# timer_mic.net
KiCad netlist of a schematic drawn in Altium Designer
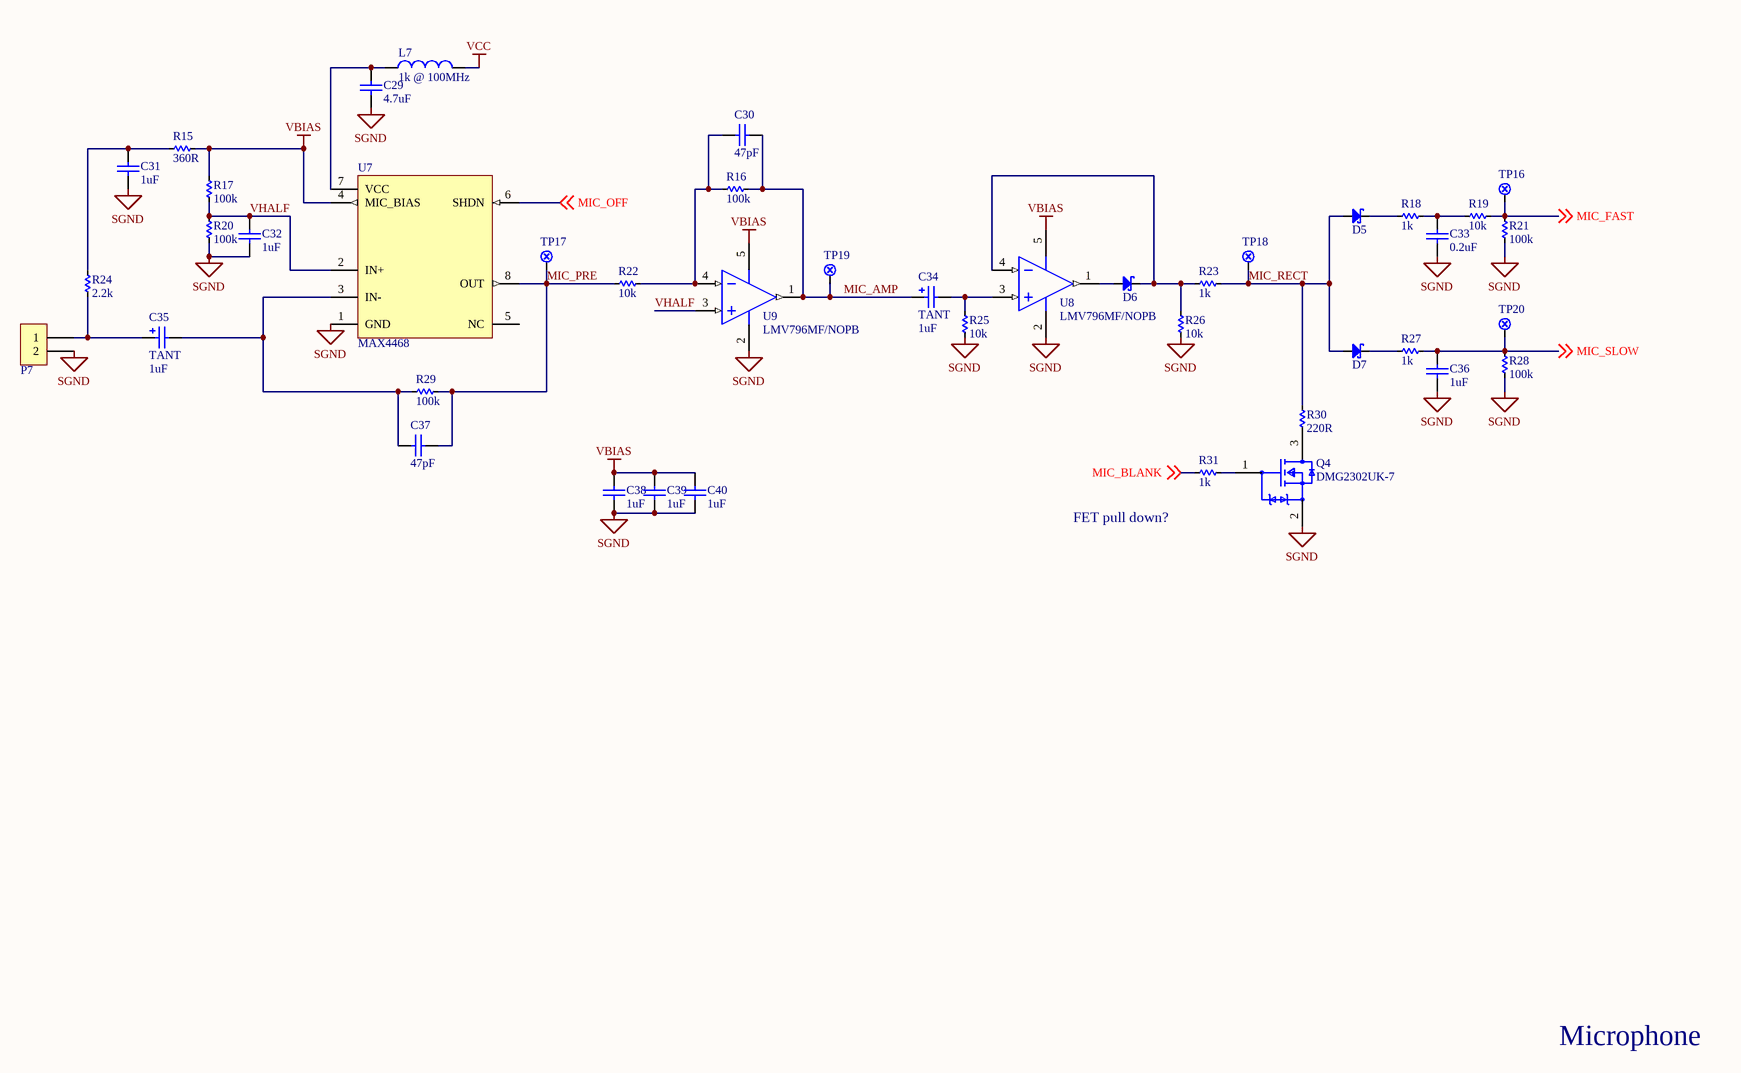
[diagram p0: timer_mic.SchDoc]

(export (version "E")
  (design (tool "Eeschema 10.0.6"))
  (components
    (comp (ref "C29")
      (value "4.7uF")
      (footprint "C0805/2012")
      (description "Capacitor")
      (fields (field (name "TOLERANCE") "x%") (field (name "VOLTAGE") "6.3V"))
      (libsource (lib "ZMPlib") (part "CAP"))
    )
    (comp (ref "C30")
      (value "47pF")
      (footprint "C0603/1608")
      (description "Capacitor")
      (fields (field (name "TOLERANCE") "x%") (field (name "VOLTAGE") "6.3V"))
      (libsource (lib "ZMPlib") (part "CAP"))
    )
    (comp (ref "C31")
      (value "1uF")
      (footprint "C0603/1608")
      (description "Capacitor")
      (fields (field (name "TOLERANCE") "x%") (field (name "VOLTAGE") "6.3V"))
      (libsource (lib "ZMPlib") (part "CAP"))
    )
    (comp (ref "C32")
      (value "1uF")
      (footprint "C0603/1608")
      (description "Capacitor")
      (fields (field (name "TOLERANCE") "x%") (field (name "VOLTAGE") "6.3V"))
      (libsource (lib "ZMPlib") (part "CAP"))
    )
    (comp (ref "C33")
      (value "0.2uF")
      (footprint "C0603/1608")
      (description "Capacitor")
      (fields (field (name "TOLERANCE") "x%") (field (name "VOLTAGE") "6.3V"))
      (libsource (lib "ZMPlib") (part "CAP"))
    )
    (comp (ref "C34")
      (value "1uF")
      (footprint "CP0805/2012")
      (description "Capacitor")
      (fields (field (name "VOLTAGE") "6.3V") (field (name "TOLERANCE") "x%") (field (name "TYPE") "TANT"))
      (libsource (lib "ZMPlib") (part "CAP_POL"))
    )
    (comp (ref "C35")
      (value "1uF")
      (footprint "CP0805/2012")
      (description "Capacitor")
      (fields (field (name "VOLTAGE") "6.3V") (field (name "TOLERANCE") "x%") (field (name "TYPE") "TANT"))
      (libsource (lib "ZMPlib") (part "CAP_POL"))
    )
    (comp (ref "C36")
      (value "1uF")
      (footprint "C0603/1608")
      (description "Capacitor")
      (fields (field (name "TOLERANCE") "x%") (field (name "VOLTAGE") "6.3V"))
      (libsource (lib "ZMPlib") (part "CAP"))
    )
    (comp (ref "C37")
      (value "47pF")
      (footprint "C0603/1608")
      (description "Capacitor")
      (fields (field (name "TOLERANCE") "x%") (field (name "VOLTAGE") "6.3V"))
      (libsource (lib "ZMPlib") (part "CAP"))
    )
    (comp (ref "C38")
      (value "1uF")
      (footprint "C0603/1608")
      (description "Capacitor")
      (fields (field (name "TOLERANCE") "x%") (field (name "VOLTAGE") "6.3V"))
      (libsource (lib "ZMPlib") (part "CAP"))
    )
    (comp (ref "C39")
      (value "1uF")
      (footprint "C0603/1608")
      (description "Capacitor")
      (fields (field (name "TOLERANCE") "x%") (field (name "VOLTAGE") "6.3V"))
      (libsource (lib "ZMPlib") (part "CAP"))
    )
    (comp (ref "C40")
      (value "1uF")
      (footprint "C0603/1608")
      (description "Capacitor")
      (fields (field (name "TOLERANCE") "x%") (field (name "VOLTAGE") "6.3V"))
      (libsource (lib "ZMPlib") (part "CAP"))
    )
    (comp (ref "D5")
      (value "DIODE_SCHOTTKY")
      (footprint "SOD-123")
      (description "Schottky Diode")
      (fields (field (name "VOLTAGE") "xV"))
      (libsource (lib "ZMPlib") (part "DIODE_SCHOTTKY"))
    )
    (comp (ref "D6")
      (value "DIODE_SCHOTTKY")
      (footprint "SOD-123")
      (description "Schottky Diode")
      (fields (field (name "VOLTAGE") "xV"))
      (libsource (lib "ZMPlib") (part "DIODE_SCHOTTKY"))
    )
    (comp (ref "D7")
      (value "DIODE_SCHOTTKY")
      (footprint "SOD-123")
      (description "Schottky Diode")
      (fields (field (name "VOLTAGE") "xV"))
      (libsource (lib "ZMPlib") (part "DIODE_SCHOTTKY"))
    )
    (comp (ref "L7")
      (value "1k @ 100MHz")
      (footprint "R0603/1608")
      (description "Inductor")
      (fields (field (name "Comment") "FERRITE"))
      (libsource (lib "ZMPlib") (part "IND"))
    )
    (comp (ref "P7")
      (value "SIL2")
      (footprint "PINS-2")
      (description "SIL package, 2 pins")
      (libsource (lib "ZMPlib") (part "SIL2"))
    )
    (comp (ref "Q4")
      (value "DMG2302UK-7")
      (footprint "FP-SOT23-MFG")
      (description "MOSFET N-CH 20V 2.8A SOT23")
      (fields
        (field (name "OCTOPART") "https://octopart.com/dmg2302uk-7-diodes+inc.-73850182")
        (field (name "MANUFACTURER") "Diodes Inc.")
      )
      (libsource (lib "Altium Content Vault") (part "87c0c04a04979492222792dd46c39c9"))
    )
    (comp (ref "R15")
      (value "360R")
      (footprint "R0603/1608")
      (description "Resistor")
      (fields (field (name "TOLERANCE") "x%") (field (name "Comment") "RES"))
      (libsource (lib "ZMPlib") (part "RES"))
    )
    (comp (ref "R16")
      (value "100k")
      (footprint "R0603/1608")
      (description "Resistor")
      (fields (field (name "TOLERANCE") "x%") (field (name "Comment") "RES"))
      (libsource (lib "ZMPlib") (part "RES"))
    )
    (comp (ref "R17")
      (value "100k")
      (footprint "R0603/1608")
      (description "Resistor")
      (fields (field (name "TOLERANCE") "x%") (field (name "Comment") "RES"))
      (libsource (lib "ZMPlib") (part "RES"))
    )
    (comp (ref "R18")
      (value "1k")
      (footprint "R0603/1608")
      (description "Resistor")
      (fields (field (name "TOLERANCE") "x%") (field (name "Comment") "RES"))
      (libsource (lib "ZMPlib") (part "RES"))
    )
    (comp (ref "R19")
      (value "10k")
      (footprint "R0603/1608")
      (description "Resistor")
      (fields (field (name "TOLERANCE") "x%") (field (name "Comment") "RES"))
      (libsource (lib "ZMPlib") (part "RES"))
    )
    (comp (ref "R20")
      (value "100k")
      (footprint "R0603/1608")
      (description "Resistor")
      (fields (field (name "TOLERANCE") "x%") (field (name "Comment") "RES"))
      (libsource (lib "ZMPlib") (part "RES"))
    )
    (comp (ref "R21")
      (value "100k")
      (footprint "R0603/1608")
      (description "Resistor")
      (fields (field (name "TOLERANCE") "x%") (field (name "Comment") "RES"))
      (libsource (lib "ZMPlib") (part "RES"))
    )
    (comp (ref "R22")
      (value "10k")
      (footprint "R0603/1608")
      (description "Resistor")
      (fields (field (name "TOLERANCE") "x%") (field (name "Comment") "RES"))
      (libsource (lib "ZMPlib") (part "RES"))
    )
    (comp (ref "R23")
      (value "1k")
      (footprint "R0603/1608")
      (description "Resistor")
      (fields (field (name "TOLERANCE") "x%") (field (name "Comment") "RES"))
      (libsource (lib "ZMPlib") (part "RES"))
    )
    (comp (ref "R24")
      (value "2.2k")
      (footprint "R0603/1608")
      (description "Resistor")
      (fields (field (name "TOLERANCE") "x%") (field (name "Comment") "RES"))
      (libsource (lib "ZMPlib") (part "RES"))
    )
    (comp (ref "R25")
      (value "10k")
      (footprint "R0603/1608")
      (description "Resistor")
      (fields (field (name "TOLERANCE") "x%") (field (name "Comment") "RES"))
      (libsource (lib "ZMPlib") (part "RES"))
    )
    (comp (ref "R26")
      (value "10k")
      (footprint "R0603/1608")
      (description "Resistor")
      (fields (field (name "TOLERANCE") "x%") (field (name "Comment") "RES"))
      (libsource (lib "ZMPlib") (part "RES"))
    )
    (comp (ref "R27")
      (value "1k")
      (footprint "R0603/1608")
      (description "Resistor")
      (fields (field (name "TOLERANCE") "x%") (field (name "Comment") "RES"))
      (libsource (lib "ZMPlib") (part "RES"))
    )
    (comp (ref "R28")
      (value "100k")
      (footprint "R0603/1608")
      (description "Resistor")
      (fields (field (name "TOLERANCE") "x%") (field (name "Comment") "RES"))
      (libsource (lib "ZMPlib") (part "RES"))
    )
    (comp (ref "R29")
      (value "100k")
      (footprint "R0603/1608")
      (description "Resistor")
      (fields (field (name "TOLERANCE") "x%") (field (name "Comment") "RES"))
      (libsource (lib "ZMPlib") (part "RES"))
    )
    (comp (ref "R30")
      (value "220R")
      (footprint "R0603/1608")
      (description "Resistor")
      (fields (field (name "TOLERANCE") "x%") (field (name "Comment") "RES"))
      (libsource (lib "ZMPlib") (part "RES"))
    )
    (comp (ref "R31")
      (value "1k")
      (footprint "R0603/1608")
      (description "Resistor")
      (fields (field (name "TOLERANCE") "x%") (field (name "Comment") "RES"))
      (libsource (lib "ZMPlib") (part "RES"))
    )
    (comp (ref "TP16")
      (value "TP")
      (footprint "TP-1.0")
      (description "Test point")
      (libsource (lib "ZMPlib") (part "TP"))
    )
    (comp (ref "TP17")
      (value "TP")
      (footprint "TP-1.0")
      (description "Test point")
      (libsource (lib "ZMPlib") (part "TP"))
    )
    (comp (ref "TP18")
      (value "TP")
      (footprint "TP-1.0")
      (description "Test point")
      (libsource (lib "ZMPlib") (part "TP"))
    )
    (comp (ref "TP19")
      (value "TP")
      (footprint "TP-1.0")
      (description "Test point")
      (libsource (lib "ZMPlib") (part "TP"))
    )
    (comp (ref "TP20")
      (value "TP")
      (footprint "TP-1.0")
      (description "Test point")
      (libsource (lib "ZMPlib") (part "TP"))
    )
    (comp (ref "U7")
      (value "MAX4468")
      (footprint "SOT23-8")
      (description "Low-Cost, Micropower, SOT23-8, Microphone\r\nPreamplifier with Complete Shutdown")
      (libsource (lib "ZMPlib") (part "MAX4468"))
    )
    (comp (ref "U8")
      (value "LMV796MF/NOPB")
      (footprint "DBV0005A_L")
      (description "17 MHz, Low Noise, CMOS Input, 1.8V Operational Amplifiers, 5-pin SOT-23, Pb-Free")
      (fields (field (name "MANUFACTURER") "Texas Instruments"))
      (libsource (lib "Altium Content Vault") (part "AMP-OPA-LM7121-5"))
    )
    (comp (ref "U9")
      (value "LMV796MF/NOPB")
      (footprint "DBV0005A_L")
      (description "17 MHz, Low Noise, CMOS Input, 1.8V Operational Amplifiers, 5-pin SOT-23, Pb-Free")
      (fields (field (name "MANUFACTURER") "Texas Instruments"))
      (libsource (lib "Altium Content Vault") (part "AMP-OPA-LM7121-5"))
    )
  )
  (nets
    (net (code "1") (name "/MIC_AMP") (class "Default")
      (node (ref "C30") (pin "2") (pinfunction "2_2") (pintype "passive"))
      (node (ref "C34") (pin "1") (pinfunction "1_1") (pintype "passive"))
      (node (ref "R16") (pin "1") (pinfunction "1_1") (pintype "passive"))
      (node (ref "TP19") (pin "0") (pinfunction "0_0") (pintype "passive"))
      (node (ref "U9") (pin "1") (pinfunction "OUT_1") (pintype "output"))
    )
    (net (code "2") (name "/MIC_PRE") (class "Default")
      (node (ref "C37") (pin "1") (pinfunction "1_1") (pintype "passive"))
      (node (ref "R22") (pin "2") (pinfunction "2_2") (pintype "passive"))
      (node (ref "R29") (pin "2") (pinfunction "2_2") (pintype "passive"))
      (node (ref "TP17") (pin "0") (pinfunction "0_0") (pintype "passive"))
      (node (ref "U7") (pin "8") (pinfunction "OUT_8") (pintype "output"))
    )
    (net (code "3") (name "/MIC_RECT") (class "Default")
      (node (ref "D5") (pin "2") (pinfunction "2_2") (pintype "passive"))
      (node (ref "D7") (pin "2") (pinfunction "2_2") (pintype "passive"))
      (node (ref "R23") (pin "1") (pinfunction "1_1") (pintype "passive"))
      (node (ref "R30") (pin "1") (pinfunction "1_1") (pintype "passive"))
      (node (ref "TP18") (pin "0") (pinfunction "0_0") (pintype "passive"))
    )
    (net (code "4") (name "/VHALF") (class "Default")
      (node (ref "C32") (pin "2") (pinfunction "2_2") (pintype "passive"))
      (node (ref "R17") (pin "2") (pinfunction "2_2") (pintype "passive"))
      (node (ref "R20") (pin "1") (pinfunction "1_1") (pintype "passive"))
      (node (ref "U7") (pin "2") (pinfunction "IN+_2") (pintype "passive"))
      (node (ref "U9") (pin "3") (pinfunction "IN+_3") (pintype "input"))
    )
    (net (code "5") (name "MIC_BLANK") (class "Default")
      (node (ref "R31") (pin "2") (pinfunction "2_2") (pintype "passive"))
    )
    (net (code "6") (name "MIC_FAST") (class "Default")
      (node (ref "R19") (pin "1") (pinfunction "1_1") (pintype "passive"))
      (node (ref "R21") (pin "1") (pinfunction "1_1") (pintype "passive"))
      (node (ref "TP16") (pin "0") (pinfunction "0_0") (pintype "passive"))
    )
    (net (code "7") (name "MIC_OFF") (class "Default")
      (node (ref "U7") (pin "6") (pinfunction "SHDN_6") (pintype "input"))
    )
    (net (code "8") (name "MIC_SLOW") (class "Default")
      (node (ref "C36") (pin "2") (pinfunction "2_2") (pintype "passive"))
      (node (ref "R27") (pin "1") (pinfunction "1_1") (pintype "passive"))
      (node (ref "R28") (pin "1") (pinfunction "1_1") (pintype "passive"))
      (node (ref "TP20") (pin "0") (pinfunction "0_0") (pintype "passive"))
    )
    (net (code "9") (name "Net-(C31-Pad2)") (class "Default")
      (node (ref "C31") (pin "2") (pinfunction "2_2") (pintype "passive"))
      (node (ref "R15") (pin "1") (pinfunction "1_1") (pintype "passive"))
      (node (ref "R24") (pin "1") (pinfunction "1_1") (pintype "passive"))
    )
    (net (code "10") (name "Net-(C33-Pad2)") (class "Default")
      (node (ref "C33") (pin "2") (pinfunction "2_2") (pintype "passive"))
      (node (ref "R18") (pin "1") (pinfunction "1_1") (pintype "passive"))
      (node (ref "R19") (pin "2") (pinfunction "2_2") (pintype "passive"))
    )
    (net (code "11") (name "Net-(C35-Pad1)") (class "Default")
      (node (ref "C35") (pin "1") (pinfunction "1_1") (pintype "passive"))
      (node (ref "P7") (pin "1") (pinfunction "1_1") (pintype "passive"))
      (node (ref "R24") (pin "2") (pinfunction "2_2") (pintype "passive"))
    )
    (net (code "12") (name "Net-(D5-Pad1)") (class "Default")
      (node (ref "D5") (pin "1") (pinfunction "1_1") (pintype "passive"))
      (node (ref "R18") (pin "2") (pinfunction "2_2") (pintype "passive"))
    )
    (net (code "13") (name "Net-(D7-Pad1)") (class "Default")
      (node (ref "D7") (pin "1") (pinfunction "1_1") (pintype "passive"))
      (node (ref "R27") (pin "2") (pinfunction "2_2") (pintype "passive"))
    )
    (net (code "14") (name "Net-(Q4-D)") (class "Default")
      (node (ref "Q4") (pin "3") (pinfunction "D_3") (pintype "passive"))
      (node (ref "R30") (pin "2") (pinfunction "2_2") (pintype "passive"))
    )
    (net (code "15") (name "Net-(Q4-G)") (class "Default")
      (node (ref "Q4") (pin "1") (pinfunction "G_1") (pintype "passive"))
      (node (ref "R31") (pin "1") (pinfunction "1_1") (pintype "passive"))
    )
    (net (code "16") (name "Net-(U7-IN-)") (class "Default")
      (node (ref "C35") (pin "2") (pinfunction "2_2") (pintype "passive"))
      (node (ref "C37") (pin "2") (pinfunction "2_2") (pintype "passive"))
      (node (ref "R29") (pin "1") (pinfunction "1_1") (pintype "passive"))
      (node (ref "U7") (pin "3") (pinfunction "IN-_3") (pintype "passive"))
    )
    (net (code "17") (name "Net-(U7-VCC)") (class "Default")
      (node (ref "C29") (pin "2") (pinfunction "2_2") (pintype "passive"))
      (node (ref "L7") (pin "1") (pinfunction "1_1") (pintype "passive"))
      (node (ref "U7") (pin "7") (pinfunction "VCC_7") (pintype "power_in"))
    )
    (net (code "18") (name "Net-(U8-IN+)") (class "Default")
      (node (ref "C34") (pin "2") (pinfunction "2_2") (pintype "passive"))
      (node (ref "R25") (pin "1") (pinfunction "1_1") (pintype "passive"))
      (node (ref "U8") (pin "3") (pinfunction "IN+_3") (pintype "input"))
    )
    (net (code "19") (name "Net-(U8-IN-)") (class "Default")
      (node (ref "D6") (pin "1") (pinfunction "1_1") (pintype "passive"))
      (node (ref "R23") (pin "2") (pinfunction "2_2") (pintype "passive"))
      (node (ref "R26") (pin "1") (pinfunction "1_1") (pintype "passive"))
      (node (ref "U8") (pin "4") (pinfunction "IN-_4") (pintype "input"))
    )
    (net (code "20") (name "Net-(U8-OUT)") (class "Default")
      (node (ref "D6") (pin "2") (pinfunction "2_2") (pintype "passive"))
      (node (ref "U8") (pin "1") (pinfunction "OUT_1") (pintype "output"))
    )
    (net (code "21") (name "Net-(U9-IN-)") (class "Default")
      (node (ref "C30") (pin "1") (pinfunction "1_1") (pintype "passive"))
      (node (ref "R16") (pin "2") (pinfunction "2_2") (pintype "passive"))
      (node (ref "R22") (pin "1") (pinfunction "1_1") (pintype "passive"))
      (node (ref "U9") (pin "4") (pinfunction "IN-_4") (pintype "input"))
    )
    (net (code "22") (name "SGND") (class "Default")
      (node (ref "C29") (pin "1") (pinfunction "1_1") (pintype "passive"))
      (node (ref "C31") (pin "1") (pinfunction "1_1") (pintype "passive"))
      (node (ref "C32") (pin "1") (pinfunction "1_1") (pintype "passive"))
      (node (ref "C33") (pin "1") (pinfunction "1_1") (pintype "passive"))
      (node (ref "C36") (pin "1") (pinfunction "1_1") (pintype "passive"))
      (node (ref "C38") (pin "1") (pinfunction "1_1") (pintype "passive"))
      (node (ref "C39") (pin "1") (pinfunction "1_1") (pintype "passive"))
      (node (ref "C40") (pin "1") (pinfunction "1_1") (pintype "passive"))
      (node (ref "P7") (pin "2") (pinfunction "2_2") (pintype "passive"))
      (node (ref "Q4") (pin "2") (pinfunction "S_2") (pintype "passive"))
      (node (ref "R20") (pin "2") (pinfunction "2_2") (pintype "passive"))
      (node (ref "R21") (pin "2") (pinfunction "2_2") (pintype "passive"))
      (node (ref "R25") (pin "2") (pinfunction "2_2") (pintype "passive"))
      (node (ref "R26") (pin "2") (pinfunction "2_2") (pintype "passive"))
      (node (ref "R28") (pin "2") (pinfunction "2_2") (pintype "passive"))
      (node (ref "U7") (pin "1") (pinfunction "GND_1") (pintype "power_in"))
      (node (ref "U8") (pin "2") (pinfunction "V-_2") (pintype "power_in"))
      (node (ref "U9") (pin "2") (pinfunction "V-_2") (pintype "power_in"))
    )
    (net (code "23") (name "VBIAS") (class "Default")
      (node (ref "C38") (pin "2") (pinfunction "2_2") (pintype "passive"))
      (node (ref "C39") (pin "2") (pinfunction "2_2") (pintype "passive"))
      (node (ref "C40") (pin "2") (pinfunction "2_2") (pintype "passive"))
      (node (ref "R15") (pin "2") (pinfunction "2_2") (pintype "passive"))
      (node (ref "R17") (pin "1") (pinfunction "1_1") (pintype "passive"))
      (node (ref "U7") (pin "4") (pinfunction "MIC_BIAS_4") (pintype "output"))
      (node (ref "U8") (pin "5") (pinfunction "V+_5") (pintype "power_in"))
      (node (ref "U9") (pin "5") (pinfunction "V+_5") (pintype "power_in"))
    )
    (net (code "24") (name "VCC") (class "Default")
      (node (ref "L7") (pin "2") (pinfunction "2_2") (pintype "passive"))
    )
    (net (code "25") (name "unconnected-(U7-NC-Pad5)") (class "Default")
      (node (ref "U7") (pin "5") (pinfunction "NC_5") (pintype "passive"))
    )
  )
)
